# micro_sd.net
KiCad netlist of a schematic drawn in Altium Designer
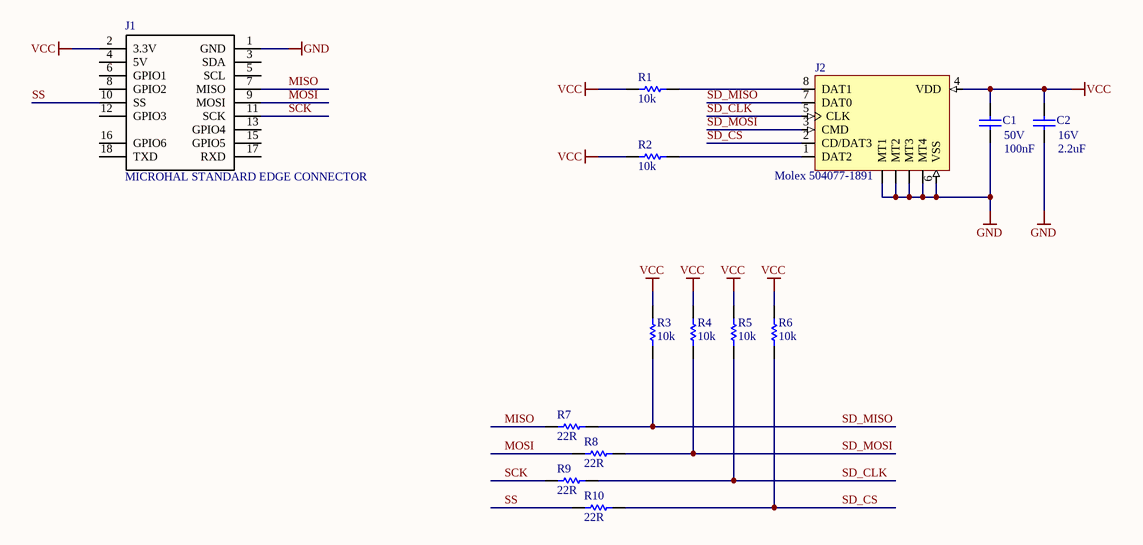
[diagram p0: micro_sd.SchDoc]

(export (version "E")
  (design (tool "Eeschema 10.0.6"))
  (components
    (comp (ref "C1")
      (value "Murata GCM188R71H104KA57D")
      (footprint "CAPC1608X90X35ML10T15")
      (description "CAP CER 0.1UF 50V 10% X7R 0603")
      (fields (field (name "CAPACITANCE") "100nF") (field (name "VOLTAGE RATING (DC)") "50V"))
      (libsource (lib "CommunityVault") (part "CMP-119667-3"))
    )
    (comp (ref "C2")
      (value "Kemet C0805C225K4RACAUTO")
      (footprint "CAPC2013X140X50ML20T25")
      (description "CAPACITOR, 0805, X7R, 16V, 2.2UF")
      (fields (field (name "CAPACITANCE") "2.2uF") (field (name "VOLTAGE RATING (DC)") "16V"))
      (libsource (lib "CommunityVault") (part "CMP-3913345-2"))
    )
    (comp (ref "J1")
      (value "MICROHAL STANDARD EDGE CONNECTOR")
      (footprint "PCB-n61ghpg3sznbl2uw6fwj-1")
      (description "microhal standard edge connector with 17 pins")
      (libsource (lib "CommunityVault") (part "CMP-6a3uyflm72uf0am1b36s-2"))
    )
    (comp (ref "J2")
      (value "Molex 504077-1891")
      (footprint "PCB-4vacospa3sytmw4kcnv2-1")
      (description "Conn Micro SD Card SKT 8 POS 1.1mm Solder RA SMD Embossed T/R 0.5A/Contact")
      (fields (field (name "MANUFACTURER") "Molex"))
      (libsource (lib "CommunityVault") (part "CMP-95805dba04df4a47-7"))
    )
    (comp (ref "R1")
      (value "Res1")
      (footprint "PCB-4hicoez4nmrdgyuwelf4-1")
      (description "Resistor; Thick Film; Res 10 Kilohms; Pwr-Rtg 0.1 W; Tol 1%; SMT; 0603")
      (fields (field (name "RESISTANCE") "10k"))
      (libsource (lib "CommunityVault") (part "CMP-51de9888c13e8e19-9"))
    )
    (comp (ref "R2")
      (value "Res1")
      (footprint "PCB-4hicoez4nmrdgyuwelf4-1")
      (description "Resistor; Thick Film; Res 10 Kilohms; Pwr-Rtg 0.1 W; Tol 1%; SMT; 0603")
      (fields (field (name "RESISTANCE") "10k"))
      (libsource (lib "CommunityVault") (part "CMP-51de9888c13e8e19-9"))
    )
    (comp (ref "R3")
      (value "Res1")
      (footprint "PCB-4hicoez4nmrdgyuwelf4-1")
      (description "Resistor; Thick Film; Res 10 Kilohms; Pwr-Rtg 0.1 W; Tol 1%; SMT; 0603")
      (fields (field (name "RESISTANCE") "10k"))
      (libsource (lib "CommunityVault") (part "CMP-51de9888c13e8e19-9"))
    )
    (comp (ref "R4")
      (value "Res1")
      (footprint "PCB-4hicoez4nmrdgyuwelf4-1")
      (description "Resistor; Thick Film; Res 10 Kilohms; Pwr-Rtg 0.1 W; Tol 1%; SMT; 0603")
      (fields (field (name "RESISTANCE") "10k"))
      (libsource (lib "CommunityVault") (part "CMP-51de9888c13e8e19-9"))
    )
    (comp (ref "R5")
      (value "Res1")
      (footprint "PCB-4hicoez4nmrdgyuwelf4-1")
      (description "Resistor; Thick Film; Res 10 Kilohms; Pwr-Rtg 0.1 W; Tol 1%; SMT; 0603")
      (fields (field (name "RESISTANCE") "10k"))
      (libsource (lib "CommunityVault") (part "CMP-51de9888c13e8e19-9"))
    )
    (comp (ref "R6")
      (value "Res1")
      (footprint "PCB-4hicoez4nmrdgyuwelf4-1")
      (description "Resistor; Thick Film; Res 10 Kilohms; Pwr-Rtg 0.1 W; Tol 1%; SMT; 0603")
      (fields (field (name "RESISTANCE") "10k"))
      (libsource (lib "CommunityVault") (part "CMP-51de9888c13e8e19-9"))
    )
    (comp (ref "R7")
      (value "Vishay Dale CRCW060322R0JNEA")
      (footprint "RESC1609X50X30ML10T20")
      (description "RES SMD 22 OHM 5% 1/10W 0603")
      (fields (field (name "RESISTANCE") "22R"))
      (libsource (lib "CommunityVault") (part "CMP-1856016-2"))
    )
    (comp (ref "R8")
      (value "Vishay Dale CRCW060322R0JNEA")
      (footprint "RESC1609X50X30ML10T20")
      (description "RES SMD 22 OHM 5% 1/10W 0603")
      (fields (field (name "RESISTANCE") "22R"))
      (libsource (lib "CommunityVault") (part "CMP-1856016-2"))
    )
    (comp (ref "R9")
      (value "Vishay Dale CRCW060322R0JNEA")
      (footprint "RESC1609X50X30ML10T20")
      (description "RES SMD 22 OHM 5% 1/10W 0603")
      (fields (field (name "RESISTANCE") "22R"))
      (libsource (lib "CommunityVault") (part "CMP-1856016-2"))
    )
    (comp (ref "R10")
      (value "Vishay Dale CRCW060322R0JNEA")
      (footprint "RESC1609X50X30ML10T20")
      (description "RES SMD 22 OHM 5% 1/10W 0603")
      (fields (field (name "RESISTANCE") "22R"))
      (libsource (lib "CommunityVault") (part "CMP-1856016-2"))
    )
  )
  (nets
    (net (code "1") (name "/MISO") (class "Default")
      (node (ref "J1") (pin "7") (pinfunction "MISO_7") (pintype "passive"))
      (node (ref "R7") (pin "2") (pinfunction "2_2") (pintype "passive"))
    )
    (net (code "2") (name "/MOSI") (class "Default")
      (node (ref "J1") (pin "9") (pinfunction "MOSI_9") (pintype "passive"))
      (node (ref "R8") (pin "2") (pinfunction "2_2") (pintype "passive"))
    )
    (net (code "3") (name "/SCK") (class "Default")
      (node (ref "J1") (pin "11") (pinfunction "SCK_11") (pintype "passive"))
      (node (ref "R9") (pin "2") (pinfunction "2_2") (pintype "passive"))
    )
    (net (code "4") (name "/SD_CLK") (class "Default")
      (node (ref "J2") (pin "5") (pinfunction "CLK_5") (pintype "input"))
      (node (ref "R5") (pin "1") (pinfunction "1_1") (pintype "passive"))
      (node (ref "R9") (pin "1") (pinfunction "1_1") (pintype "passive"))
    )
    (net (code "5") (name "/SD_CS") (class "Default")
      (node (ref "J2") (pin "2") (pinfunction "CD/DAT3_2") (pintype "passive"))
      (node (ref "R10") (pin "1") (pinfunction "1_1") (pintype "passive"))
      (node (ref "R6") (pin "1") (pinfunction "1_1") (pintype "passive"))
    )
    (net (code "6") (name "/SD_MISO") (class "Default")
      (node (ref "J2") (pin "7") (pinfunction "DAT0_7") (pintype "passive"))
      (node (ref "R3") (pin "1") (pinfunction "1_1") (pintype "passive"))
      (node (ref "R7") (pin "1") (pinfunction "1_1") (pintype "passive"))
    )
    (net (code "7") (name "/SD_MOSI") (class "Default")
      (node (ref "J2") (pin "3") (pinfunction "CMD_3") (pintype "input"))
      (node (ref "R4") (pin "1") (pinfunction "1_1") (pintype "passive"))
      (node (ref "R8") (pin "1") (pinfunction "1_1") (pintype "passive"))
    )
    (net (code "8") (name "/SS") (class "Default")
      (node (ref "J1") (pin "10") (pinfunction "SS_10") (pintype "passive"))
      (node (ref "R10") (pin "2") (pinfunction "2_2") (pintype "passive"))
    )
    (net (code "9") (name "GND") (class "Default")
      (node (ref "C1") (pin "1") (pinfunction "1_1") (pintype "passive"))
      (node (ref "C2") (pin "2") (pinfunction "2_2") (pintype "passive"))
      (node (ref "J1") (pin "1") (pinfunction "GND_1") (pintype "passive"))
      (node (ref "J2") (pin "6") (pinfunction "VSS_6") (pintype "input"))
      (node (ref "J2") (pin "MT1") (pinfunction "MT1_MT1") (pintype "passive"))
      (node (ref "J2") (pin "MT2") (pinfunction "MT2_MT2") (pintype "passive"))
      (node (ref "J2") (pin "MT3") (pinfunction "MT3_MT3") (pintype "passive"))
      (node (ref "J2") (pin "MT4") (pinfunction "MT4_MT4") (pintype "passive"))
    )
    (net (code "10") (name "Net-(J2-DAT1)") (class "Default")
      (node (ref "J2") (pin "8") (pinfunction "DAT1_8") (pintype "passive"))
      (node (ref "R1") (pin "1") (pinfunction "1_1") (pintype "passive"))
    )
    (net (code "11") (name "Net-(J2-DAT2)") (class "Default")
      (node (ref "J2") (pin "1") (pinfunction "DAT2_1") (pintype "passive"))
      (node (ref "R2") (pin "1") (pinfunction "1_1") (pintype "passive"))
    )
    (net (code "12") (name "VCC") (class "Default")
      (node (ref "C1") (pin "2") (pinfunction "2_2") (pintype "passive"))
      (node (ref "C2") (pin "1") (pinfunction "1_1") (pintype "passive"))
      (node (ref "J1") (pin "2") (pinfunction "3.3V_2") (pintype "passive"))
      (node (ref "J2") (pin "4") (pinfunction "VDD_4") (pintype "input"))
      (node (ref "R1") (pin "2") (pinfunction "2_2") (pintype "passive"))
      (node (ref "R2") (pin "2") (pinfunction "2_2") (pintype "passive"))
      (node (ref "R3") (pin "2") (pinfunction "2_2") (pintype "passive"))
      (node (ref "R4") (pin "2") (pinfunction "2_2") (pintype "passive"))
      (node (ref "R5") (pin "2") (pinfunction "2_2") (pintype "passive"))
      (node (ref "R6") (pin "2") (pinfunction "2_2") (pintype "passive"))
    )
    (net (code "13") (name "unconnected-(J1-5V-Pad4)") (class "Default")
      (node (ref "J1") (pin "4") (pinfunction "5V_4") (pintype "passive"))
    )
    (net (code "14") (name "unconnected-(J1-GPIO1-Pad6)") (class "Default")
      (node (ref "J1") (pin "6") (pinfunction "GPIO1_6") (pintype "passive"))
    )
    (net (code "15") (name "unconnected-(J1-GPIO2-Pad8)") (class "Default")
      (node (ref "J1") (pin "8") (pinfunction "GPIO2_8") (pintype "passive"))
    )
    (net (code "16") (name "unconnected-(J1-GPIO3-Pad12)") (class "Default")
      (node (ref "J1") (pin "12") (pinfunction "GPIO3_12") (pintype "passive"))
    )
    (net (code "17") (name "unconnected-(J1-GPIO4-Pad13)") (class "Default")
      (node (ref "J1") (pin "13") (pinfunction "GPIO4_13") (pintype "passive"))
    )
    (net (code "18") (name "unconnected-(J1-GPIO5-Pad15)") (class "Default")
      (node (ref "J1") (pin "15") (pinfunction "GPIO5_15") (pintype "passive"))
    )
    (net (code "19") (name "unconnected-(J1-GPIO6-Pad16)") (class "Default")
      (node (ref "J1") (pin "16") (pinfunction "GPIO6_16") (pintype "passive"))
    )
    (net (code "20") (name "unconnected-(J1-RXD-Pad17)") (class "Default")
      (node (ref "J1") (pin "17") (pinfunction "RXD_17") (pintype "passive"))
    )
    (net (code "21") (name "unconnected-(J1-SCL-Pad5)") (class "Default")
      (node (ref "J1") (pin "5") (pinfunction "SCL_5") (pintype "passive"))
    )
    (net (code "22") (name "unconnected-(J1-SDA-Pad3)") (class "Default")
      (node (ref "J1") (pin "3") (pinfunction "SDA_3") (pintype "passive"))
    )
    (net (code "23") (name "unconnected-(J1-TXD-Pad18)") (class "Default")
      (node (ref "J1") (pin "18") (pinfunction "TXD_18") (pintype "passive"))
    )
  )
)
